# RH006_1.net
KiCad netlist of a schematic drawn in EAGLE
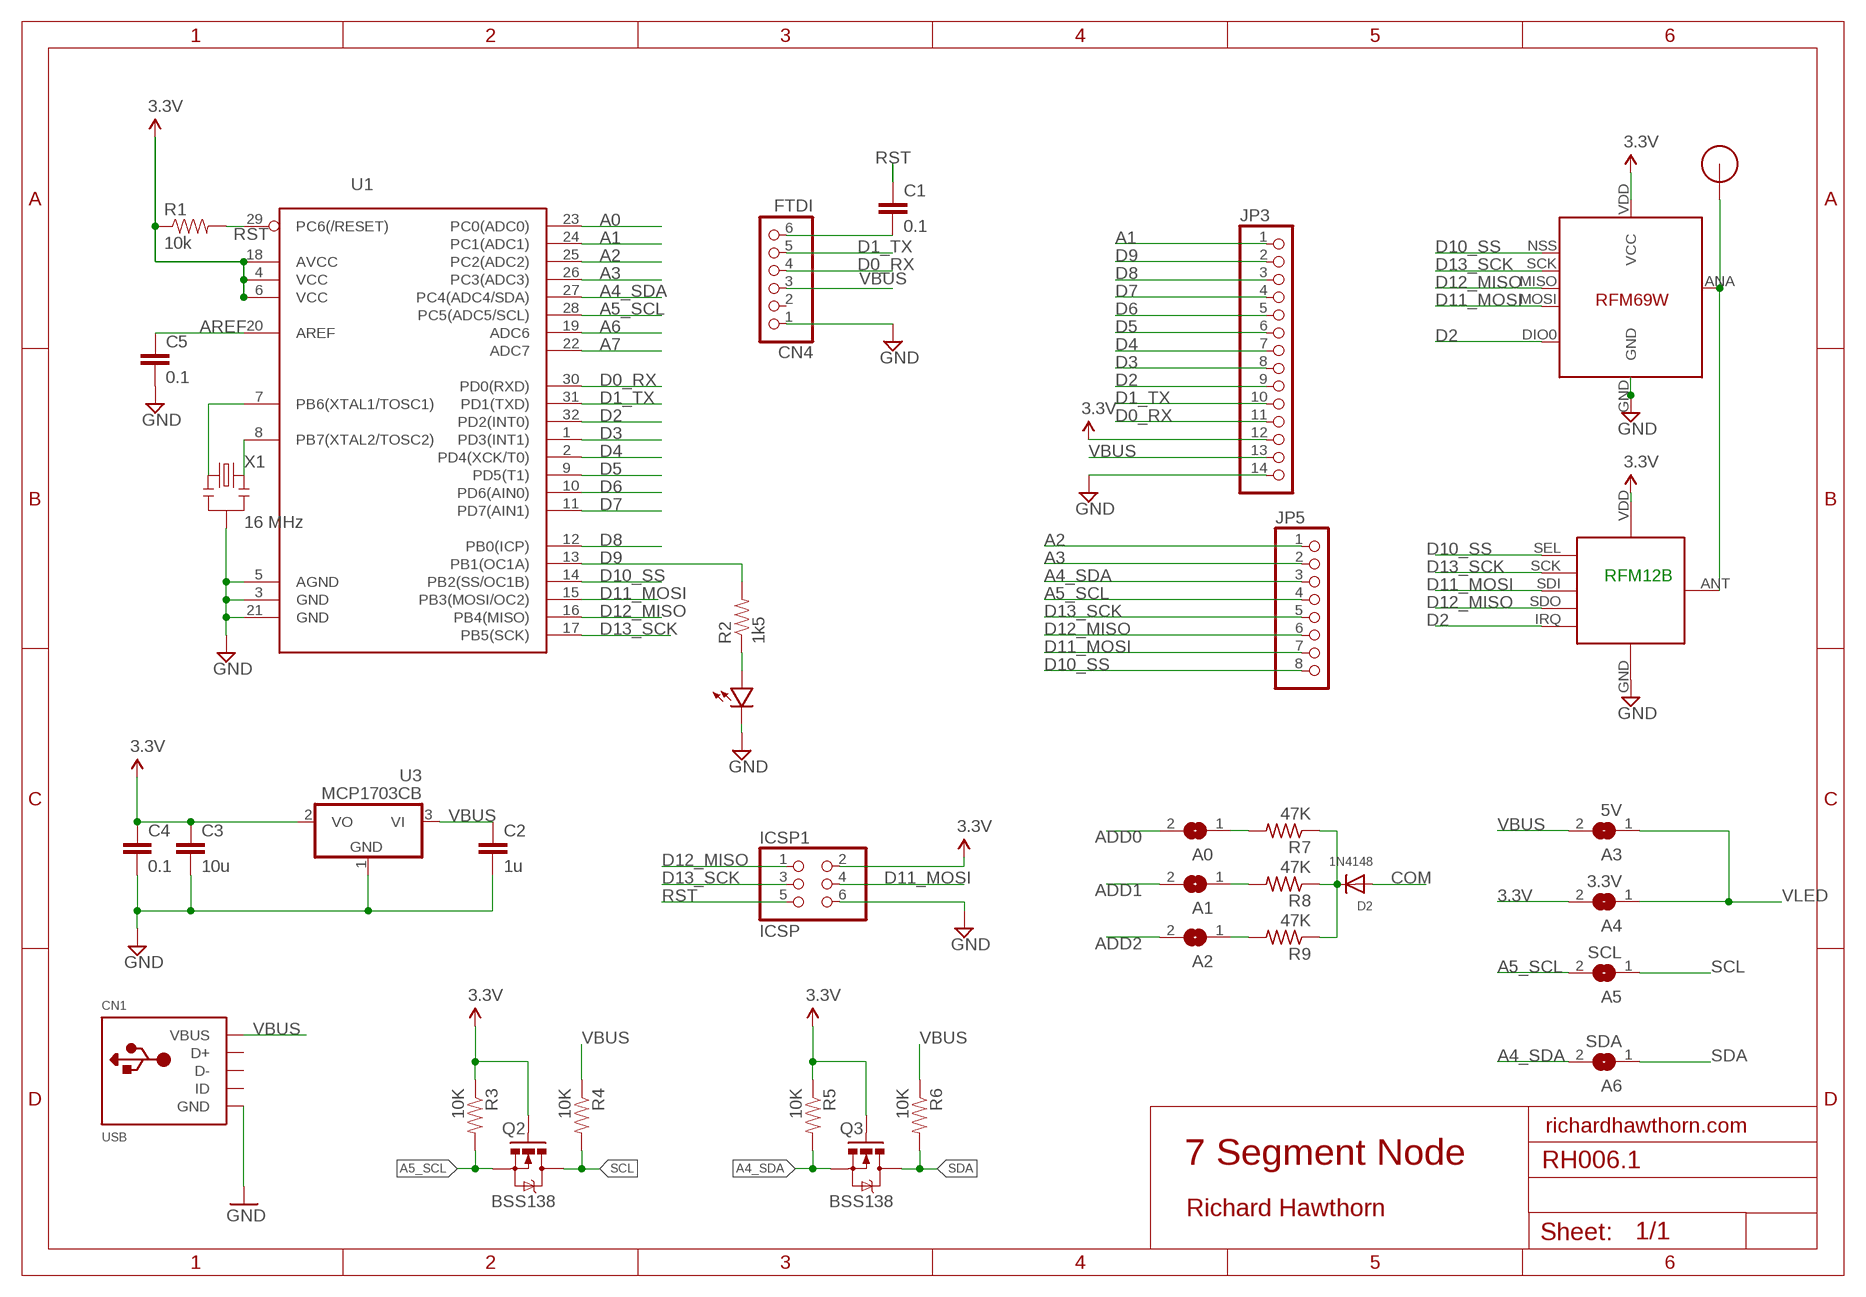
[diagram p0: schematic, sheet 1, part 1 of 2]
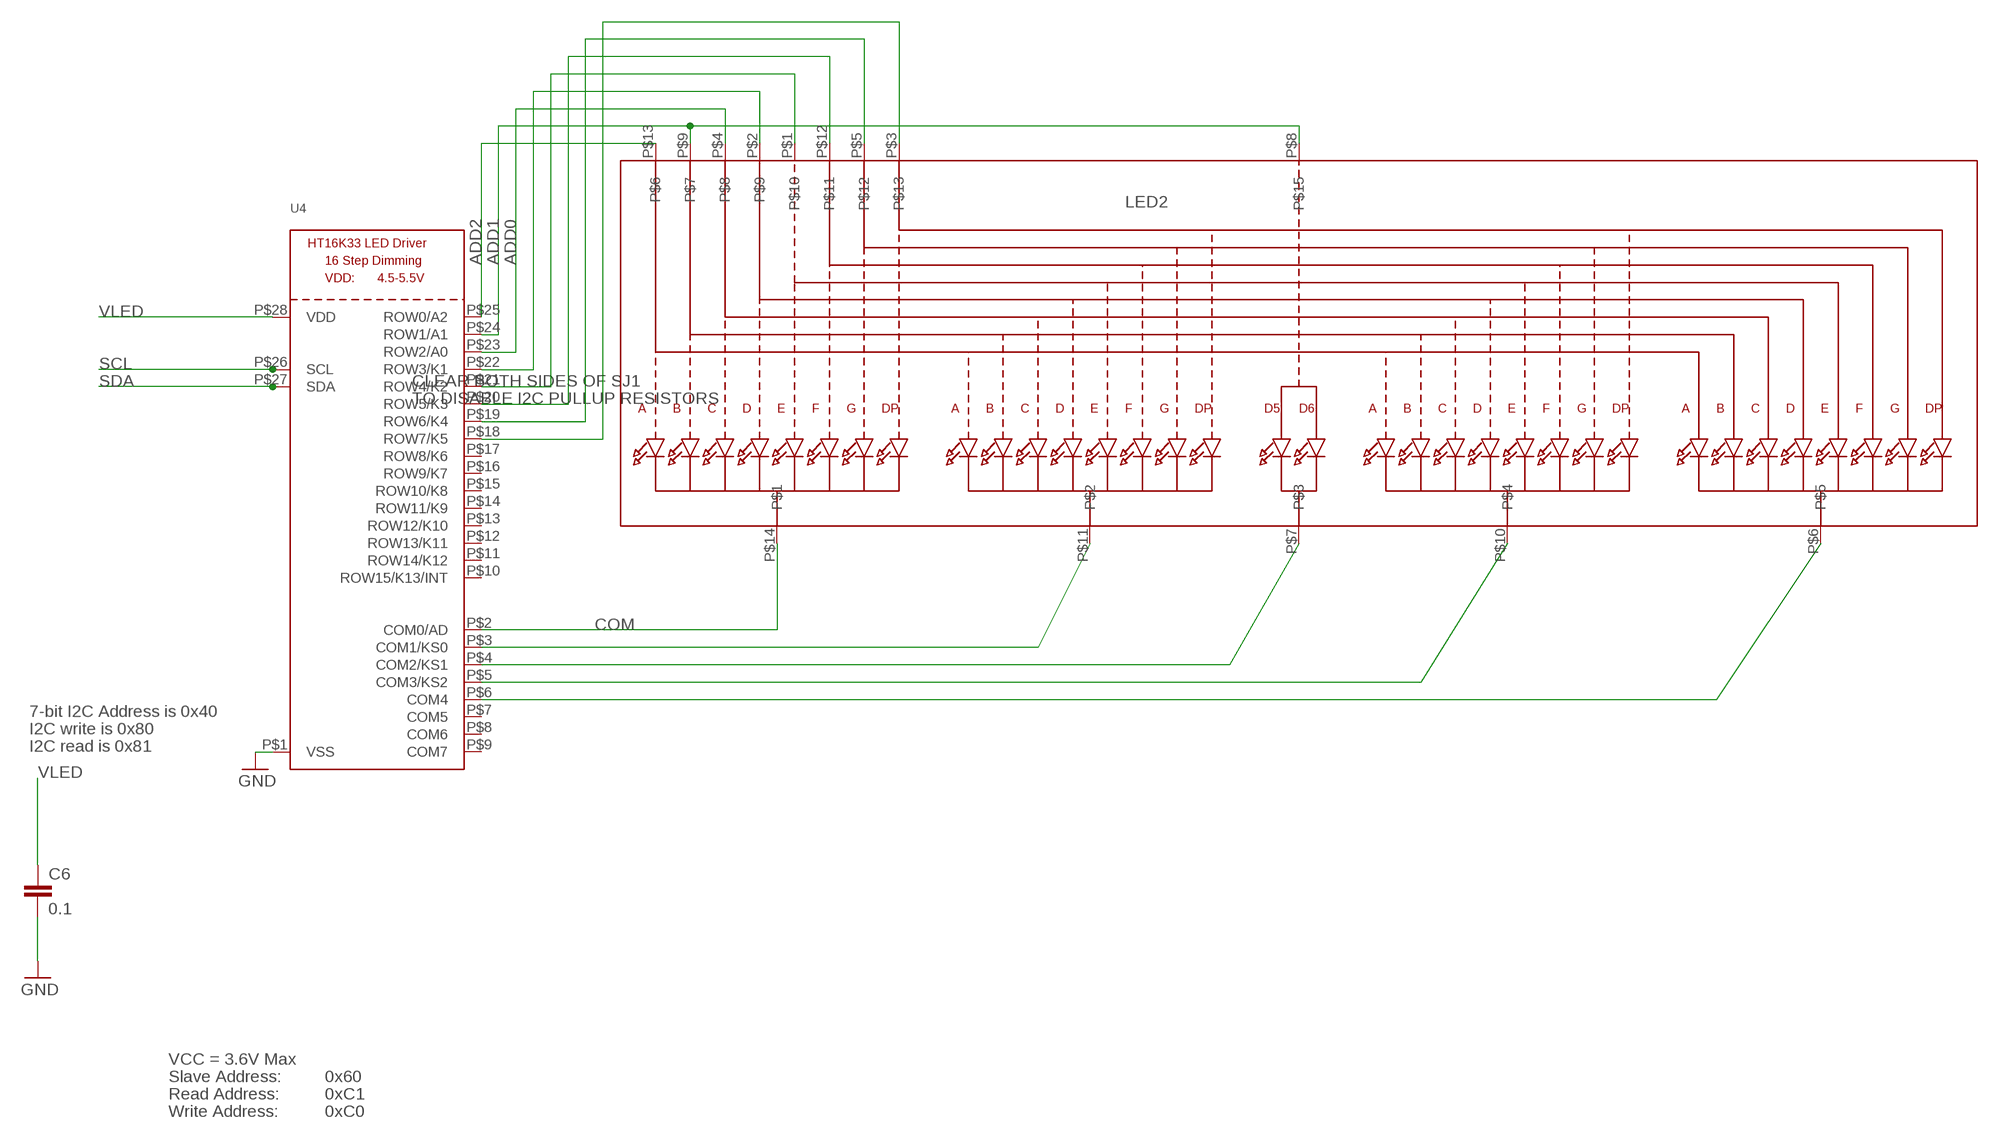
[diagram p1: schematic, sheet 1, part 2 of 2]

(export (version "E")
  (design (tool "Eeschema 10.0.6"))
  (components
    (comp (ref "A0")
      (value "SOLDERJUMPERREFLOW_NOPASTE")
      (footprint "eagle-import:SOLDERJUMPER_REFLOW_NOPASTE")
      (libsource (lib "eagle-import") (part "SOLDERJUMPERREFLOW_NOPASTE"))
    )
    (comp (ref "A1")
      (value "SOLDERJUMPERREFLOW_NOPASTE")
      (footprint "eagle-import:SOLDERJUMPER_REFLOW_NOPASTE")
      (libsource (lib "eagle-import") (part "SOLDERJUMPERREFLOW_NOPASTE"))
    )
    (comp (ref "A2")
      (value "SOLDERJUMPERREFLOW_NOPASTE")
      (footprint "eagle-import:SOLDERJUMPER_REFLOW_NOPASTE")
      (libsource (lib "eagle-import") (part "SOLDERJUMPERREFLOW_NOPASTE"))
    )
    (comp (ref "A3")
      (value "5V")
      (footprint "eagle-import:SOLDERJUMPER_REFLOW_NOPASTE")
      (libsource (lib "eagle-import") (part "SOLDERJUMPERREFLOW_NOPASTE"))
    )
    (comp (ref "A4")
      (value "3.3V")
      (footprint "eagle-import:SOLDERJUMPER_REFLOW_NOPASTE")
      (libsource (lib "eagle-import") (part "SOLDERJUMPERREFLOW_NOPASTE"))
    )
    (comp (ref "A5")
      (value "SCL")
      (footprint "eagle-import:SOLDERJUMPER_REFLOW_NOPASTE")
      (libsource (lib "eagle-import") (part "SOLDERJUMPERREFLOW_NOPASTE"))
    )
    (comp (ref "A6")
      (value "SDA")
      (footprint "eagle-import:SOLDERJUMPER_REFLOW_NOPASTE")
      (libsource (lib "eagle-import") (part "SOLDERJUMPERREFLOW_NOPASTE"))
    )
    (comp (ref "C1")
      (value "0.1")
      (footprint "eagle-import:0603-CAP")
      (libsource (lib "eagle-import") (part "CAP0603-CAP"))
    )
    (comp (ref "C2")
      (value "1u")
      (footprint "eagle-import:0603-CAP")
      (libsource (lib "eagle-import") (part "CAP0603-CAP"))
    )
    (comp (ref "C3")
      (value "10u")
      (footprint "eagle-import:0805-CAP")
      (libsource (lib "eagle-import") (part "CAP0805-CAP"))
    )
    (comp (ref "C4")
      (value "0.1")
      (footprint "eagle-import:0603-CAP")
      (libsource (lib "eagle-import") (part "CAP0603-CAP"))
    )
    (comp (ref "C5")
      (value "0.1")
      (footprint "eagle-import:0603-CAP")
      (libsource (lib "eagle-import") (part "CAP0603-CAP"))
    )
    (comp (ref "C6")
      (value "0.1")
      (footprint "eagle-import:0603-CAP")
      (libsource (lib "eagle-import") (part "CAP0603-CAP"))
    )
    (comp (ref "CN1")
      (value "USB")
      (footprint "eagle-import:USB-MINIB")
      (libsource (lib "eagle-import") (part "USBMINIB"))
    )
    (comp (ref "CN4")
      (value "FTDI")
      (footprint "eagle-import:1X06")
      (libsource (lib "eagle-import") (part "PINHD-1X6"))
    )
    (comp (ref "D2")
      (value "1N4148")
      (footprint "eagle-import:SOD-323F")
      (libsource (lib "eagle-import") (part "DIODESOD-323F"))
    )
    (comp (ref "ICSP1")
      (value "ICSP")
      (footprint "eagle-import:2X03")
      (libsource (lib "eagle-import") (part "PINHD-2X3"))
    )
    (comp (ref "JP3")
      (value "PINHD-1X14")
      (footprint "eagle-import:1X14")
      (libsource (lib "eagle-import") (part "PINHD-1X14"))
    )
    (comp (ref "JP5")
      (value "PINHD-1X8")
      (footprint "eagle-import:1X08")
      (libsource (lib "eagle-import") (part "PINHD-1X8"))
    )
    (comp (ref "LED1")
      (value "LED0603")
      (footprint "eagle-import:0603-LED")
      (libsource (lib "eagle-import") (part "LED0603"))
    )
    (comp (ref "LED2")
      (value "DISP_SEGMENT_4DIGIT_BL-Q56C43")
      (footprint "eagle-import:SEGMENT-BL-Q56C43")
      (libsource (lib "eagle-import") (part "DISP_SEGMENT_4DIGIT_BL-Q56C43"))
    )
    (comp (ref "Q2")
      (value "BSS138")
      (footprint "eagle-import:SOT23-3")
      (libsource (lib "eagle-import") (part "MOSFET-NCHANNELSMD"))
    )
    (comp (ref "Q3")
      (value "BSS138")
      (footprint "eagle-import:SOT23-3")
      (libsource (lib "eagle-import") (part "MOSFET-NCHANNELSMD"))
    )
    (comp (ref "R1")
      (value "10k")
      (footprint "eagle-import:0603-RES")
      (libsource (lib "eagle-import") (part "RESISTOR0603-RES"))
    )
    (comp (ref "R2")
      (value "1k5")
      (footprint "eagle-import:0805")
      (libsource (lib "eagle-import") (part "RESISTOR0805"))
    )
    (comp (ref "R3")
      (value "10K")
      (footprint "eagle-import:0603-RES")
      (libsource (lib "eagle-import") (part "SparkFun_RESISTOR0603-RES"))
    )
    (comp (ref "R4")
      (value "10K")
      (footprint "eagle-import:0603-RES")
      (libsource (lib "eagle-import") (part "SparkFun_RESISTOR0603-RES"))
    )
    (comp (ref "R5")
      (value "10K")
      (footprint "eagle-import:0603-RES")
      (libsource (lib "eagle-import") (part "SparkFun_RESISTOR0603-RES"))
    )
    (comp (ref "R6")
      (value "10K")
      (footprint "eagle-import:0603-RES")
      (libsource (lib "eagle-import") (part "SparkFun_RESISTOR0603-RES"))
    )
    (comp (ref "R7")
      (value "47K")
      (footprint "eagle-import:R0805")
      (libsource (lib "eagle-import") (part "R-US_R0805"))
    )
    (comp (ref "R8")
      (value "47K")
      (footprint "eagle-import:R0805")
      (libsource (lib "eagle-import") (part "R-US_R0805"))
    )
    (comp (ref "R9")
      (value "47K")
      (footprint "eagle-import:R0805")
      (libsource (lib "eagle-import") (part "R-US_R0805"))
    )
    (comp (ref "RF1")
      (value "RFM12B")
      (footprint "eagle-import:RFM12B-MINPADS")
      (libsource (lib "eagle-import") (part "RFM12B_MINPADS"))
    )
    (comp (ref "RF2")
      (value "RFM69")
      (footprint "eagle-import:RFM69W-MINPADS")
      (libsource (lib "eagle-import") (part "RFM69"))
    )
    (comp (ref "U$1")
      (value "RFM12B_ANTENNA")
      (footprint "eagle-import:RFM12B-ANTENNA")
      (libsource (lib "eagle-import") (part "RFM12B_ANTENNA"))
    )
    (comp (ref "U1")
      (value "ATMega-328")
      (footprint "eagle-import:TQFP32-08")
      (libsource (lib "eagle-import") (part "ATMEGA168/328TQFP32"))
    )
    (comp (ref "U3")
      (value "MCP1703CB")
      (footprint "eagle-import:SOT23")
      (libsource (lib "eagle-import") (part "MCP1703CB"))
    )
    (comp (ref "U4")
      (value "HT16K33_SOP28")
      (footprint "eagle-import:SOP28_300MIL")
      (libsource (lib "eagle-import") (part "HT16K33_SOP28"))
    )
    (comp (ref "X1")
      (value "16 MHz")
      (footprint "eagle-import:RESONATOR-SMD")
      (libsource (lib "eagle-import") (part "RESONATORSMD"))
    )
  )
  (nets
    (net (code "1") (name "/A0") (class "Default")
      (node (ref "U1") (pin "23") (pinfunction "PC0(ADC0)_23") (pintype "bidirectional"))
    )
    (net (code "2") (name "/A1") (class "Default")
      (node (ref "JP3") (pin "1") (pinfunction "1_1") (pintype "passive"))
      (node (ref "U1") (pin "24") (pinfunction "PC1(ADC1)_24") (pintype "bidirectional"))
    )
    (net (code "3") (name "/A2") (class "Default")
      (node (ref "JP5") (pin "1") (pinfunction "1_1") (pintype "passive"))
      (node (ref "U1") (pin "25") (pinfunction "PC2(ADC2)_25") (pintype "bidirectional"))
    )
    (net (code "4") (name "/A3") (class "Default")
      (node (ref "JP5") (pin "2") (pinfunction "2_2") (pintype "passive"))
      (node (ref "U1") (pin "26") (pinfunction "PC3(ADC3)_26") (pintype "bidirectional"))
    )
    (net (code "5") (name "/A6") (class "Default")
      (node (ref "U1") (pin "19") (pinfunction "ADC6_19") (pintype "bidirectional"))
    )
    (net (code "6") (name "/A7") (class "Default")
      (node (ref "U1") (pin "22") (pinfunction "ADC7_22") (pintype "bidirectional"))
    )
    (net (code "7") (name "/ADD0") (class "Default")
      (node (ref "A0") (pin "2") (pinfunction "2_2") (pintype "passive"))
      (node (ref "LED2") (pin "P$4") (pinfunction "P$8_P$4") (pintype "bidirectional"))
      (node (ref "U4") (pin "P$23") (pinfunction "ROW2/A0_P$23") (pintype "bidirectional"))
    )
    (net (code "8") (name "/ADD1") (class "Default")
      (node (ref "A1") (pin "2") (pinfunction "2_2") (pintype "passive"))
      (node (ref "LED2") (pin "P$8") (pinfunction "P$15_P$8") (pintype "bidirectional"))
      (node (ref "LED2") (pin "P$9") (pinfunction "P$7_P$9") (pintype "bidirectional"))
      (node (ref "U4") (pin "P$24") (pinfunction "ROW1/A1_P$24") (pintype "bidirectional"))
    )
    (net (code "9") (name "/ADD2") (class "Default")
      (node (ref "A2") (pin "2") (pinfunction "2_2") (pintype "passive"))
      (node (ref "LED2") (pin "P$13") (pinfunction "P$6_P$13") (pintype "bidirectional"))
      (node (ref "U4") (pin "P$25") (pinfunction "ROW0/A2_P$25") (pintype "bidirectional"))
    )
    (net (code "10") (name "/AREF") (class "Default")
      (node (ref "C5") (pin "1") (pinfunction "1_1") (pintype "passive"))
      (node (ref "U1") (pin "20") (pinfunction "AREF_20") (pintype "bidirectional"))
    )
    (net (code "11") (name "/COM") (class "Default")
      (node (ref "D2") (pin "A") (pinfunction "A_A") (pintype "passive"))
      (node (ref "LED2") (pin "P$14") (pinfunction "P$1_P$14") (pintype "bidirectional"))
      (node (ref "U4") (pin "P$2") (pinfunction "COM0/AD_P$2") (pintype "bidirectional"))
    )
    (net (code "12") (name "/D0_RX") (class "Default")
      (node (ref "CN4") (pin "4") (pinfunction "4_4") (pintype "passive"))
      (node (ref "JP3") (pin "11") (pinfunction "11_11") (pintype "passive"))
      (node (ref "U1") (pin "30") (pinfunction "PD0(RXD)_30") (pintype "bidirectional"))
    )
    (net (code "13") (name "/D1_TX") (class "Default")
      (node (ref "CN4") (pin "5") (pinfunction "5_5") (pintype "passive"))
      (node (ref "JP3") (pin "10") (pinfunction "10_10") (pintype "passive"))
      (node (ref "U1") (pin "31") (pinfunction "PD1(TXD)_31") (pintype "bidirectional"))
    )
    (net (code "14") (name "/D2") (class "Default")
      (node (ref "JP3") (pin "9") (pinfunction "9_9") (pintype "passive"))
      (node (ref "RF1") (pin "IRQ") (pinfunction "IRQ_IRQ") (pintype "bidirectional"))
      (node (ref "RF2") (pin "DIO0") (pinfunction "DIO0_DIO0") (pintype "open_collector"))
      (node (ref "U1") (pin "32") (pinfunction "PD2(INT0)_32") (pintype "bidirectional"))
    )
    (net (code "15") (name "/D3") (class "Default")
      (node (ref "JP3") (pin "8") (pinfunction "8_8") (pintype "passive"))
      (node (ref "U1") (pin "1") (pinfunction "PD3(INT1)_1") (pintype "bidirectional"))
    )
    (net (code "16") (name "/D4") (class "Default")
      (node (ref "JP3") (pin "7") (pinfunction "7_7") (pintype "passive"))
      (node (ref "U1") (pin "2") (pinfunction "PD4(XCK/T0)_2") (pintype "bidirectional"))
    )
    (net (code "17") (name "/D5") (class "Default")
      (node (ref "JP3") (pin "6") (pinfunction "6_6") (pintype "passive"))
      (node (ref "U1") (pin "9") (pinfunction "PD5(T1)_9") (pintype "bidirectional"))
    )
    (net (code "18") (name "/D6") (class "Default")
      (node (ref "JP3") (pin "5") (pinfunction "5_5") (pintype "passive"))
      (node (ref "U1") (pin "10") (pinfunction "PD6(AIN0)_10") (pintype "bidirectional"))
    )
    (net (code "19") (name "/D7") (class "Default")
      (node (ref "JP3") (pin "4") (pinfunction "4_4") (pintype "passive"))
      (node (ref "U1") (pin "11") (pinfunction "PD7(AIN1)_11") (pintype "bidirectional"))
    )
    (net (code "20") (name "/D8") (class "Default")
      (node (ref "JP3") (pin "3") (pinfunction "3_3") (pintype "passive"))
      (node (ref "U1") (pin "12") (pinfunction "PB0(ICP)_12") (pintype "bidirectional"))
    )
    (net (code "21") (name "/D9") (class "Default")
      (node (ref "JP3") (pin "2") (pinfunction "2_2") (pintype "passive"))
      (node (ref "R2") (pin "2") (pinfunction "2_2") (pintype "passive"))
      (node (ref "U1") (pin "13") (pinfunction "PB1(OC1A)_13") (pintype "bidirectional"))
    )
    (net (code "22") (name "/D10_SS") (class "Default")
      (node (ref "JP5") (pin "8") (pinfunction "8_8") (pintype "passive"))
      (node (ref "RF1") (pin "SEL") (pinfunction "SEL_SEL") (pintype "bidirectional"))
      (node (ref "RF2") (pin "NSS") (pinfunction "SEL_NSS") (pintype "input"))
      (node (ref "U1") (pin "14") (pinfunction "PB2(SS/OC1B)_14") (pintype "bidirectional"))
    )
    (net (code "23") (name "/D11_MOSI") (class "Default")
      (node (ref "ICSP1") (pin "4") (pinfunction "4_4") (pintype "passive"))
      (node (ref "JP5") (pin "7") (pinfunction "7_7") (pintype "passive"))
      (node (ref "RF1") (pin "SDI") (pinfunction "SDI/MOSI_SDI") (pintype "bidirectional"))
      (node (ref "RF2") (pin "MOSI") (pinfunction "MOSI_MOSI") (pintype "output"))
      (node (ref "U1") (pin "15") (pinfunction "PB3(MOSI/OC2)_15") (pintype "bidirectional"))
    )
    (net (code "24") (name "/D12_MISO") (class "Default")
      (node (ref "ICSP1") (pin "1") (pinfunction "1_1") (pintype "passive"))
      (node (ref "JP5") (pin "6") (pinfunction "6_6") (pintype "passive"))
      (node (ref "RF1") (pin "SDO") (pinfunction "SDO/MISO_SDO") (pintype "bidirectional"))
      (node (ref "RF2") (pin "MISO") (pinfunction "MISO_MISO") (pintype "input"))
      (node (ref "U1") (pin "16") (pinfunction "PB4(MISO)_16") (pintype "bidirectional"))
    )
    (net (code "25") (name "/D13_SCK") (class "Default")
      (node (ref "ICSP1") (pin "3") (pinfunction "3_3") (pintype "passive"))
      (node (ref "JP5") (pin "5") (pinfunction "5_5") (pintype "passive"))
      (node (ref "RF1") (pin "SCK") (pinfunction "SCK_SCK") (pintype "bidirectional"))
      (node (ref "RF2") (pin "SCK") (pinfunction "SCK_SCK") (pintype "input"))
      (node (ref "U1") (pin "17") (pinfunction "PB5(SCK)_17") (pintype "bidirectional"))
    )
    (net (code "26") (name "/RST") (class "Default")
      (node (ref "C1") (pin "1") (pinfunction "1_1") (pintype "passive"))
      (node (ref "ICSP1") (pin "5") (pinfunction "5_5") (pintype "passive"))
      (node (ref "R1") (pin "2") (pinfunction "2_2") (pintype "passive"))
      (node (ref "U1") (pin "29") (pinfunction "PC6(/RESET)_29") (pintype "bidirectional"))
    )
    (net (code "27") (name "/VBUS") (class "Default")
      (node (ref "A3") (pin "2") (pinfunction "2_2") (pintype "passive"))
      (node (ref "C2") (pin "1") (pinfunction "1_1") (pintype "passive"))
      (node (ref "CN1") (pin "VBUS") (pinfunction "VBUS_VBUS") (pintype "power_in"))
      (node (ref "CN4") (pin "3") (pinfunction "3_3") (pintype "passive"))
      (node (ref "JP3") (pin "13") (pinfunction "13_13") (pintype "passive"))
      (node (ref "R4") (pin "1") (pinfunction "1_1") (pintype "passive"))
      (node (ref "R6") (pin "1") (pinfunction "1_1") (pintype "passive"))
      (node (ref "U3") (pin "3") (pinfunction "VI_3") (pintype "input"))
    )
    (net (code "28") (name "/VLED") (class "Default")
      (node (ref "A3") (pin "1") (pinfunction "1_1") (pintype "passive"))
      (node (ref "A4") (pin "1") (pinfunction "1_1") (pintype "passive"))
      (node (ref "C6") (pin "1") (pinfunction "1_1") (pintype "passive"))
      (node (ref "U4") (pin "P$28") (pinfunction "VDD_P$28") (pintype "bidirectional"))
    )
    (net (code "29") (name "3.3V") (class "Default")
      (node (ref "A4") (pin "2") (pinfunction "2_2") (pintype "passive"))
      (node (ref "C3") (pin "1") (pinfunction "1_1") (pintype "passive"))
      (node (ref "C4") (pin "1") (pinfunction "1_1") (pintype "passive"))
      (node (ref "ICSP1") (pin "2") (pinfunction "2_2") (pintype "passive"))
      (node (ref "JP3") (pin "12") (pinfunction "12_12") (pintype "passive"))
      (node (ref "Q2") (pin "1") (pinfunction "G_1") (pintype "passive"))
      (node (ref "Q3") (pin "1") (pinfunction "G_1") (pintype "passive"))
      (node (ref "R1") (pin "1") (pinfunction "1_1") (pintype "passive"))
      (node (ref "R3") (pin "1") (pinfunction "1_1") (pintype "passive"))
      (node (ref "R5") (pin "1") (pinfunction "1_1") (pintype "passive"))
      (node (ref "RF1") (pin "VDD") (pinfunction "VDD_VDD") (pintype "bidirectional"))
      (node (ref "RF2") (pin "VDD") (pinfunction "VCC_VDD") (pintype "power_in"))
      (node (ref "U1") (pin "18") (pinfunction "AVCC_18") (pintype "bidirectional"))
      (node (ref "U1") (pin "4") (pinfunction "VCC_4") (pintype "bidirectional"))
      (node (ref "U1") (pin "6") (pinfunction "VCC_6") (pintype "bidirectional"))
      (node (ref "U3") (pin "2") (pinfunction "VO_2") (pintype "passive"))
    )
    (net (code "30") (name "A4_SDA") (class "Default")
      (node (ref "A6") (pin "2") (pinfunction "2_2") (pintype "passive"))
      (node (ref "JP5") (pin "3") (pinfunction "3_3") (pintype "passive"))
      (node (ref "Q3") (pin "2") (pinfunction "S_2") (pintype "passive"))
      (node (ref "R5") (pin "2") (pinfunction "2_2") (pintype "passive"))
      (node (ref "U1") (pin "27") (pinfunction "PC4(ADC4/SDA)_27") (pintype "bidirectional"))
    )
    (net (code "31") (name "A5_SCL") (class "Default")
      (node (ref "A5") (pin "2") (pinfunction "2_2") (pintype "passive"))
      (node (ref "JP5") (pin "4") (pinfunction "4_4") (pintype "passive"))
      (node (ref "Q2") (pin "2") (pinfunction "S_2") (pintype "passive"))
      (node (ref "R3") (pin "2") (pinfunction "2_2") (pintype "passive"))
      (node (ref "U1") (pin "28") (pinfunction "PC5(ADC5/SCL)_28") (pintype "bidirectional"))
    )
    (net (code "32") (name "GND") (class "Default")
      (node (ref "C2") (pin "2") (pinfunction "2_2") (pintype "passive"))
      (node (ref "C3") (pin "2") (pinfunction "2_2") (pintype "passive"))
      (node (ref "C4") (pin "2") (pinfunction "2_2") (pintype "passive"))
      (node (ref "C5") (pin "2") (pinfunction "2_2") (pintype "passive"))
      (node (ref "C6") (pin "2") (pinfunction "2_2") (pintype "passive"))
      (node (ref "CN1") (pin "GND") (pinfunction "GND_GND") (pintype "power_in"))
      (node (ref "CN4") (pin "1") (pinfunction "1_1") (pintype "passive"))
      (node (ref "ICSP1") (pin "6") (pinfunction "6_6") (pintype "passive"))
      (node (ref "JP3") (pin "14") (pinfunction "14_14") (pintype "passive"))
      (node (ref "LED1") (pin "MINUS") (pinfunction "MINUS_MINUS") (pintype "passive"))
      (node (ref "RF1") (pin "GND") (pinfunction "GND_GND") (pintype "bidirectional"))
      (node (ref "RF2") (pin "GND") (pinfunction "GND_GND") (pintype "power_in"))
      (node (ref "U1") (pin "21") (pinfunction "GND_21") (pintype "bidirectional"))
      (node (ref "U1") (pin "3") (pinfunction "GND_3") (pintype "bidirectional"))
      (node (ref "U1") (pin "5") (pinfunction "AGND_5") (pintype "bidirectional"))
      (node (ref "U3") (pin "1") (pinfunction "GND_1") (pintype "passive"))
      (node (ref "U4") (pin "P$1") (pinfunction "VSS_P$1") (pintype "bidirectional"))
      (node (ref "X1") (pin "2") (pinfunction "2_2") (pintype "passive"))
    )
    (net (code "33") (name "Net-(A0-Pad1)") (class "Default")
      (node (ref "A0") (pin "1") (pinfunction "1_1") (pintype "passive"))
      (node (ref "R7") (pin "2") (pinfunction "2_2") (pintype "passive"))
    )
    (net (code "34") (name "Net-(A1-Pad1)") (class "Default")
      (node (ref "A1") (pin "1") (pinfunction "1_1") (pintype "passive"))
      (node (ref "R8") (pin "2") (pinfunction "2_2") (pintype "passive"))
    )
    (net (code "35") (name "Net-(A2-Pad1)") (class "Default")
      (node (ref "A2") (pin "1") (pinfunction "1_1") (pintype "passive"))
      (node (ref "R9") (pin "2") (pinfunction "2_2") (pintype "passive"))
    )
    (net (code "36") (name "Net-(C1-Pad2)") (class "Default")
      (node (ref "C1") (pin "2") (pinfunction "2_2") (pintype "passive"))
      (node (ref "CN4") (pin "6") (pinfunction "6_6") (pintype "passive"))
    )
    (net (code "37") (name "Net-(D2-PadC)") (class "Default")
      (node (ref "D2") (pin "C") (pinfunction "C_C") (pintype "passive"))
      (node (ref "R7") (pin "1") (pinfunction "1_1") (pintype "passive"))
      (node (ref "R8") (pin "1") (pinfunction "1_1") (pintype "passive"))
      (node (ref "R9") (pin "1") (pinfunction "1_1") (pintype "passive"))
    )
    (net (code "38") (name "Net-(LED1-PadPLUS)") (class "Default")
      (node (ref "LED1") (pin "PLUS") (pinfunction "PLUS_PLUS") (pintype "passive"))
      (node (ref "R2") (pin "1") (pinfunction "1_1") (pintype "passive"))
    )
    (net (code "39") (name "Net-(LED2-P$2)") (class "Default")
      (node (ref "LED2") (pin "P$11") (pinfunction "P$2_P$11") (pintype "bidirectional"))
      (node (ref "U4") (pin "P$3") (pinfunction "COM1/KS0_P$3") (pintype "bidirectional"))
    )
    (net (code "40") (name "Net-(LED2-P$3)") (class "Default")
      (node (ref "LED2") (pin "P$7") (pinfunction "P$3_P$7") (pintype "bidirectional"))
      (node (ref "U4") (pin "P$4") (pinfunction "COM2/KS1_P$4") (pintype "bidirectional"))
    )
    (net (code "41") (name "Net-(LED2-P$4)") (class "Default")
      (node (ref "LED2") (pin "P$10") (pinfunction "P$4_P$10") (pintype "bidirectional"))
      (node (ref "U4") (pin "P$5") (pinfunction "COM3/KS2_P$5") (pintype "bidirectional"))
    )
    (net (code "42") (name "Net-(LED2-P$5)") (class "Default")
      (node (ref "LED2") (pin "P$6") (pinfunction "P$5_P$6") (pintype "bidirectional"))
      (node (ref "U4") (pin "P$6") (pinfunction "COM4_P$6") (pintype "bidirectional"))
    )
    (net (code "43") (name "Net-(LED2-P$9)") (class "Default")
      (node (ref "LED2") (pin "P$2") (pinfunction "P$9_P$2") (pintype "bidirectional"))
      (node (ref "U4") (pin "P$22") (pinfunction "ROW3/K1_P$22") (pintype "bidirectional"))
    )
    (net (code "44") (name "Net-(LED2-P$10)") (class "Default")
      (node (ref "LED2") (pin "P$1") (pinfunction "P$10_P$1") (pintype "bidirectional"))
      (node (ref "U4") (pin "P$21") (pinfunction "ROW4/K2_P$21") (pintype "bidirectional"))
    )
    (net (code "45") (name "Net-(LED2-P$11)") (class "Default")
      (node (ref "LED2") (pin "P$12") (pinfunction "P$11_P$12") (pintype "bidirectional"))
      (node (ref "U4") (pin "P$20") (pinfunction "ROW5/K3_P$20") (pintype "bidirectional"))
    )
    (net (code "46") (name "Net-(LED2-P$12)") (class "Default")
      (node (ref "LED2") (pin "P$5") (pinfunction "P$12_P$5") (pintype "bidirectional"))
      (node (ref "U4") (pin "P$19") (pinfunction "ROW6/K4_P$19") (pintype "bidirectional"))
    )
    (net (code "47") (name "Net-(LED2-P$13)") (class "Default")
      (node (ref "LED2") (pin "P$3") (pinfunction "P$13_P$3") (pintype "bidirectional"))
      (node (ref "U4") (pin "P$18") (pinfunction "ROW7/K5_P$18") (pintype "bidirectional"))
    )
    (net (code "48") (name "Net-(RF2-ANT)") (class "Default")
      (node (ref "RF1") (pin "ANT") (pinfunction "ANT_ANT") (pintype "bidirectional"))
      (node (ref "RF2") (pin "ANA") (pinfunction "ANT_ANA") (pintype "passive"))
      (node (ref "U$1") (pin "P$1") (pinfunction "1_P$1") (pintype "bidirectional"))
    )
    (net (code "49") (name "Net-(U1-PB6(XTAL1{slash}TOSC1))") (class "Default")
      (node (ref "U1") (pin "7") (pinfunction "PB6(XTAL1/TOSC1)_7") (pintype "bidirectional"))
      (node (ref "X1") (pin "1") (pinfunction "1_1") (pintype "passive"))
    )
    (net (code "50") (name "Net-(U1-PB7(XTAL2{slash}TOSC2))") (class "Default")
      (node (ref "U1") (pin "8") (pinfunction "PB7(XTAL2/TOSC2)_8") (pintype "bidirectional"))
      (node (ref "X1") (pin "3") (pinfunction "3_3") (pintype "passive"))
    )
    (net (code "51") (name "SCL") (class "Default")
      (node (ref "A5") (pin "1") (pinfunction "1_1") (pintype "passive"))
      (node (ref "Q2") (pin "3") (pinfunction "D_3") (pintype "passive"))
      (node (ref "R4") (pin "2") (pinfunction "2_2") (pintype "passive"))
      (node (ref "U4") (pin "P$26") (pinfunction "SCL_P$26") (pintype "bidirectional"))
    )
    (net (code "52") (name "SDA") (class "Default")
      (node (ref "A6") (pin "1") (pinfunction "1_1") (pintype "passive"))
      (node (ref "Q3") (pin "3") (pinfunction "D_3") (pintype "passive"))
      (node (ref "R6") (pin "2") (pinfunction "2_2") (pintype "passive"))
      (node (ref "U4") (pin "P$27") (pinfunction "SDA_P$27") (pintype "bidirectional"))
    )
    (net (code "53") (name "unconnected-(CN1-PadD+)") (class "Default")
      (node (ref "CN1") (pin "D+") (pinfunction "D+_D+") (pintype "bidirectional"))
    )
    (net (code "54") (name "unconnected-(CN1-PadD-)") (class "Default")
      (node (ref "CN1") (pin "D-") (pinfunction "D-_D-") (pintype "bidirectional"))
    )
    (net (code "55") (name "unconnected-(CN1-PadID)") (class "Default")
      (node (ref "CN1") (pin "ID") (pinfunction "ID_ID") (pintype "bidirectional"))
    )
    (net (code "56") (name "unconnected-(CN4-Pad2)") (class "Default")
      (node (ref "CN4") (pin "2") (pinfunction "2_2") (pintype "passive"))
    )
    (net (code "57") (name "unconnected-(U4-COM5-PadP$7)") (class "Default")
      (node (ref "U4") (pin "P$7") (pinfunction "COM5_P$7") (pintype "bidirectional"))
    )
    (net (code "58") (name "unconnected-(U4-COM6-PadP$8)") (class "Default")
      (node (ref "U4") (pin "P$8") (pinfunction "COM6_P$8") (pintype "bidirectional"))
    )
    (net (code "59") (name "unconnected-(U4-COM7-PadP$9)") (class "Default")
      (node (ref "U4") (pin "P$9") (pinfunction "COM7_P$9") (pintype "bidirectional"))
    )
    (net (code "60") (name "unconnected-(U4-ROW8{slash}K6-PadP$17)") (class "Default")
      (node (ref "U4") (pin "P$17") (pinfunction "ROW8/K6_P$17") (pintype "bidirectional"))
    )
    (net (code "61") (name "unconnected-(U4-ROW9{slash}K7-PadP$16)") (class "Default")
      (node (ref "U4") (pin "P$16") (pinfunction "ROW9/K7_P$16") (pintype "bidirectional"))
    )
    (net (code "62") (name "unconnected-(U4-ROW10{slash}K8-PadP$15)") (class "Default")
      (node (ref "U4") (pin "P$15") (pinfunction "ROW10/K8_P$15") (pintype "bidirectional"))
    )
    (net (code "63") (name "unconnected-(U4-ROW11{slash}K9-PadP$14)") (class "Default")
      (node (ref "U4") (pin "P$14") (pinfunction "ROW11/K9_P$14") (pintype "bidirectional"))
    )
    (net (code "64") (name "unconnected-(U4-ROW12{slash}K10-PadP$13)") (class "Default")
      (node (ref "U4") (pin "P$13") (pinfunction "ROW12/K10_P$13") (pintype "bidirectional"))
    )
    (net (code "65") (name "unconnected-(U4-ROW13{slash}K11-PadP$12)") (class "Default")
      (node (ref "U4") (pin "P$12") (pinfunction "ROW13/K11_P$12") (pintype "bidirectional"))
    )
    (net (code "66") (name "unconnected-(U4-ROW14{slash}K12-PadP$11)") (class "Default")
      (node (ref "U4") (pin "P$11") (pinfunction "ROW14/K12_P$11") (pintype "bidirectional"))
    )
    (net (code "67") (name "unconnected-(U4-ROW15{slash}K13{slash}INT-PadP$10)") (class "Default")
      (node (ref "U4") (pin "P$10") (pinfunction "ROW15/K13/INT_P$10") (pintype "bidirectional"))
    )
  )
)
